# Sheet1.net
KiCad netlist of a schematic drawn in Altium Designer
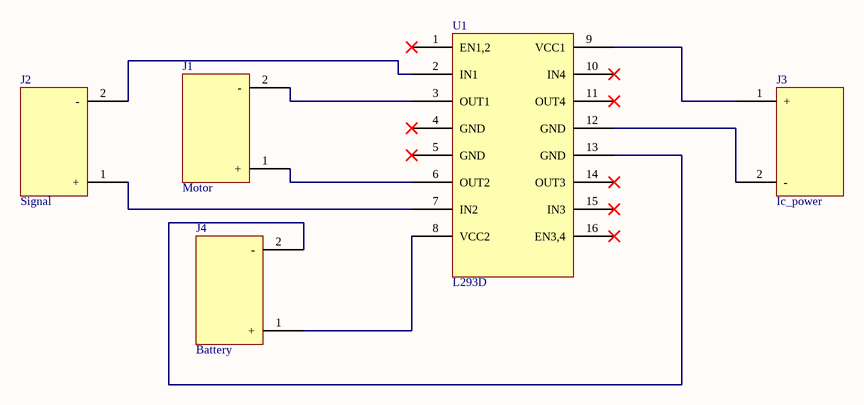
[diagram p0: Sheet1.SchDoc]

(export (version "E")
  (design (tool "Eeschema 10.0.6"))
  (components
    (comp (ref "J1")
      (value "Motor")
      (footprint "HEAD")
      (fields
        (field (name "MANUFACTURER") "Sullins")
        (field (name "MANUFACTURER PART NUMBER") "PPPC021LFBN-RC")
      )
      (libsource (lib "LED_Component") (part "PPPC021LFBN-RC"))
    )
    (comp (ref "J2")
      (value "Signal")
      (footprint "HEAD")
      (fields
        (field (name "MANUFACTURER") "Sullins")
        (field (name "MANUFACTURER PART NUMBER") "PPPC021LFBN-RC")
      )
      (libsource (lib "LED_Component") (part "PPPC021LFBN-RC"))
    )
    (comp (ref "J3")
      (value "Ic_power")
      (footprint "HEAD")
      (fields
        (field (name "MANUFACTURER") "Sullins")
        (field (name "MANUFACTURER PART NUMBER") "PPPC021LFBN-RC")
      )
      (libsource (lib "") (part "PPPC021LFBN-RC_1"))
    )
    (comp (ref "J4")
      (value "Battery")
      (footprint "HEAD")
      (fields
        (field (name "MANUFACTURER") "Sullins")
        (field (name "MANUFACTURER PART NUMBER") "PPPC021LFBN-RC")
      )
      (libsource (lib "LED_Component") (part "PPPC021LFBN-RC"))
    )
    (comp (ref "U1")
      (value "L293D")
      (footprint "L293d")
      (description "Half Bridge Based Peripheral Driver, 1.2A, PDIP16")
      (fields (field (name "MANUFACTURER") "STMicroelectronics"))
      (libsource (lib "L293d") (part "L293D"))
    )
  )
  (nets
    (net (code "1") (name "Net-(J1-+)") (class "Default")
      (node (ref "J1") (pin "1") (pinfunction "+_1") (pintype "passive"))
      (node (ref "U1") (pin "6") (pinfunction "OUT2_6") (pintype "passive"))
    )
    (net (code "2") (name "Net-(J1--)") (class "Default")
      (node (ref "J1") (pin "2") (pinfunction "-_2") (pintype "passive"))
      (node (ref "U1") (pin "3") (pinfunction "OUT1_3") (pintype "passive"))
    )
    (net (code "3") (name "Net-(J2-+)") (class "Default")
      (node (ref "J2") (pin "1") (pinfunction "+_1") (pintype "passive"))
      (node (ref "U1") (pin "7") (pinfunction "IN2_7") (pintype "passive"))
    )
    (net (code "4") (name "Net-(J2--)") (class "Default")
      (node (ref "J2") (pin "2") (pinfunction "-_2") (pintype "passive"))
      (node (ref "U1") (pin "2") (pinfunction "IN1_2") (pintype "passive"))
    )
    (net (code "5") (name "Net-(J3-+)") (class "Default")
      (node (ref "J3") (pin "1") (pinfunction "+_1") (pintype "passive"))
      (node (ref "U1") (pin "9") (pinfunction "VCC1_9") (pintype "passive"))
    )
    (net (code "6") (name "Net-(J3--)") (class "Default")
      (node (ref "J3") (pin "2") (pinfunction "-_2") (pintype "passive"))
      (node (ref "U1") (pin "12") (pinfunction "GND_12") (pintype "passive"))
    )
    (net (code "7") (name "Net-(J4-+)") (class "Default")
      (node (ref "J4") (pin "1") (pinfunction "+_1") (pintype "passive"))
      (node (ref "U1") (pin "8") (pinfunction "VCC2_8") (pintype "passive"))
    )
    (net (code "8") (name "Net-(J4--)") (class "Default")
      (node (ref "J4") (pin "2") (pinfunction "-_2") (pintype "passive"))
      (node (ref "U1") (pin "13") (pinfunction "GND_13") (pintype "passive"))
    )
    (net (code "9") (name "unconnected-(U1-EN1,2-Pad1)") (class "Default")
      (node (ref "U1") (pin "1") (pinfunction "EN1,2_1") (pintype "passive+no_connect"))
    )
    (net (code "10") (name "unconnected-(U1-EN3,4-Pad16)") (class "Default")
      (node (ref "U1") (pin "16") (pinfunction "EN3,4_16") (pintype "passive+no_connect"))
    )
    (net (code "11") (name "unconnected-(U1-GND-Pad4)") (class "Default")
      (node (ref "U1") (pin "4") (pinfunction "GND_4") (pintype "passive+no_connect"))
    )
    (net (code "12") (name "unconnected-(U1-GND-Pad5)") (class "Default")
      (node (ref "U1") (pin "5") (pinfunction "GND_5") (pintype "passive+no_connect"))
    )
    (net (code "13") (name "unconnected-(U1-IN3-Pad15)") (class "Default")
      (node (ref "U1") (pin "15") (pinfunction "IN3_15") (pintype "passive+no_connect"))
    )
    (net (code "14") (name "unconnected-(U1-IN4-Pad10)") (class "Default")
      (node (ref "U1") (pin "10") (pinfunction "IN4_10") (pintype "passive+no_connect"))
    )
    (net (code "15") (name "unconnected-(U1-OUT3-Pad14)") (class "Default")
      (node (ref "U1") (pin "14") (pinfunction "OUT3_14") (pintype "passive+no_connect"))
    )
    (net (code "16") (name "unconnected-(U1-OUT4-Pad11)") (class "Default")
      (node (ref "U1") (pin "11") (pinfunction "OUT4_11") (pintype "passive+no_connect"))
    )
  )
)
